# LEDDrive1.net
KiCad netlist of a schematic drawn in Altium Designer
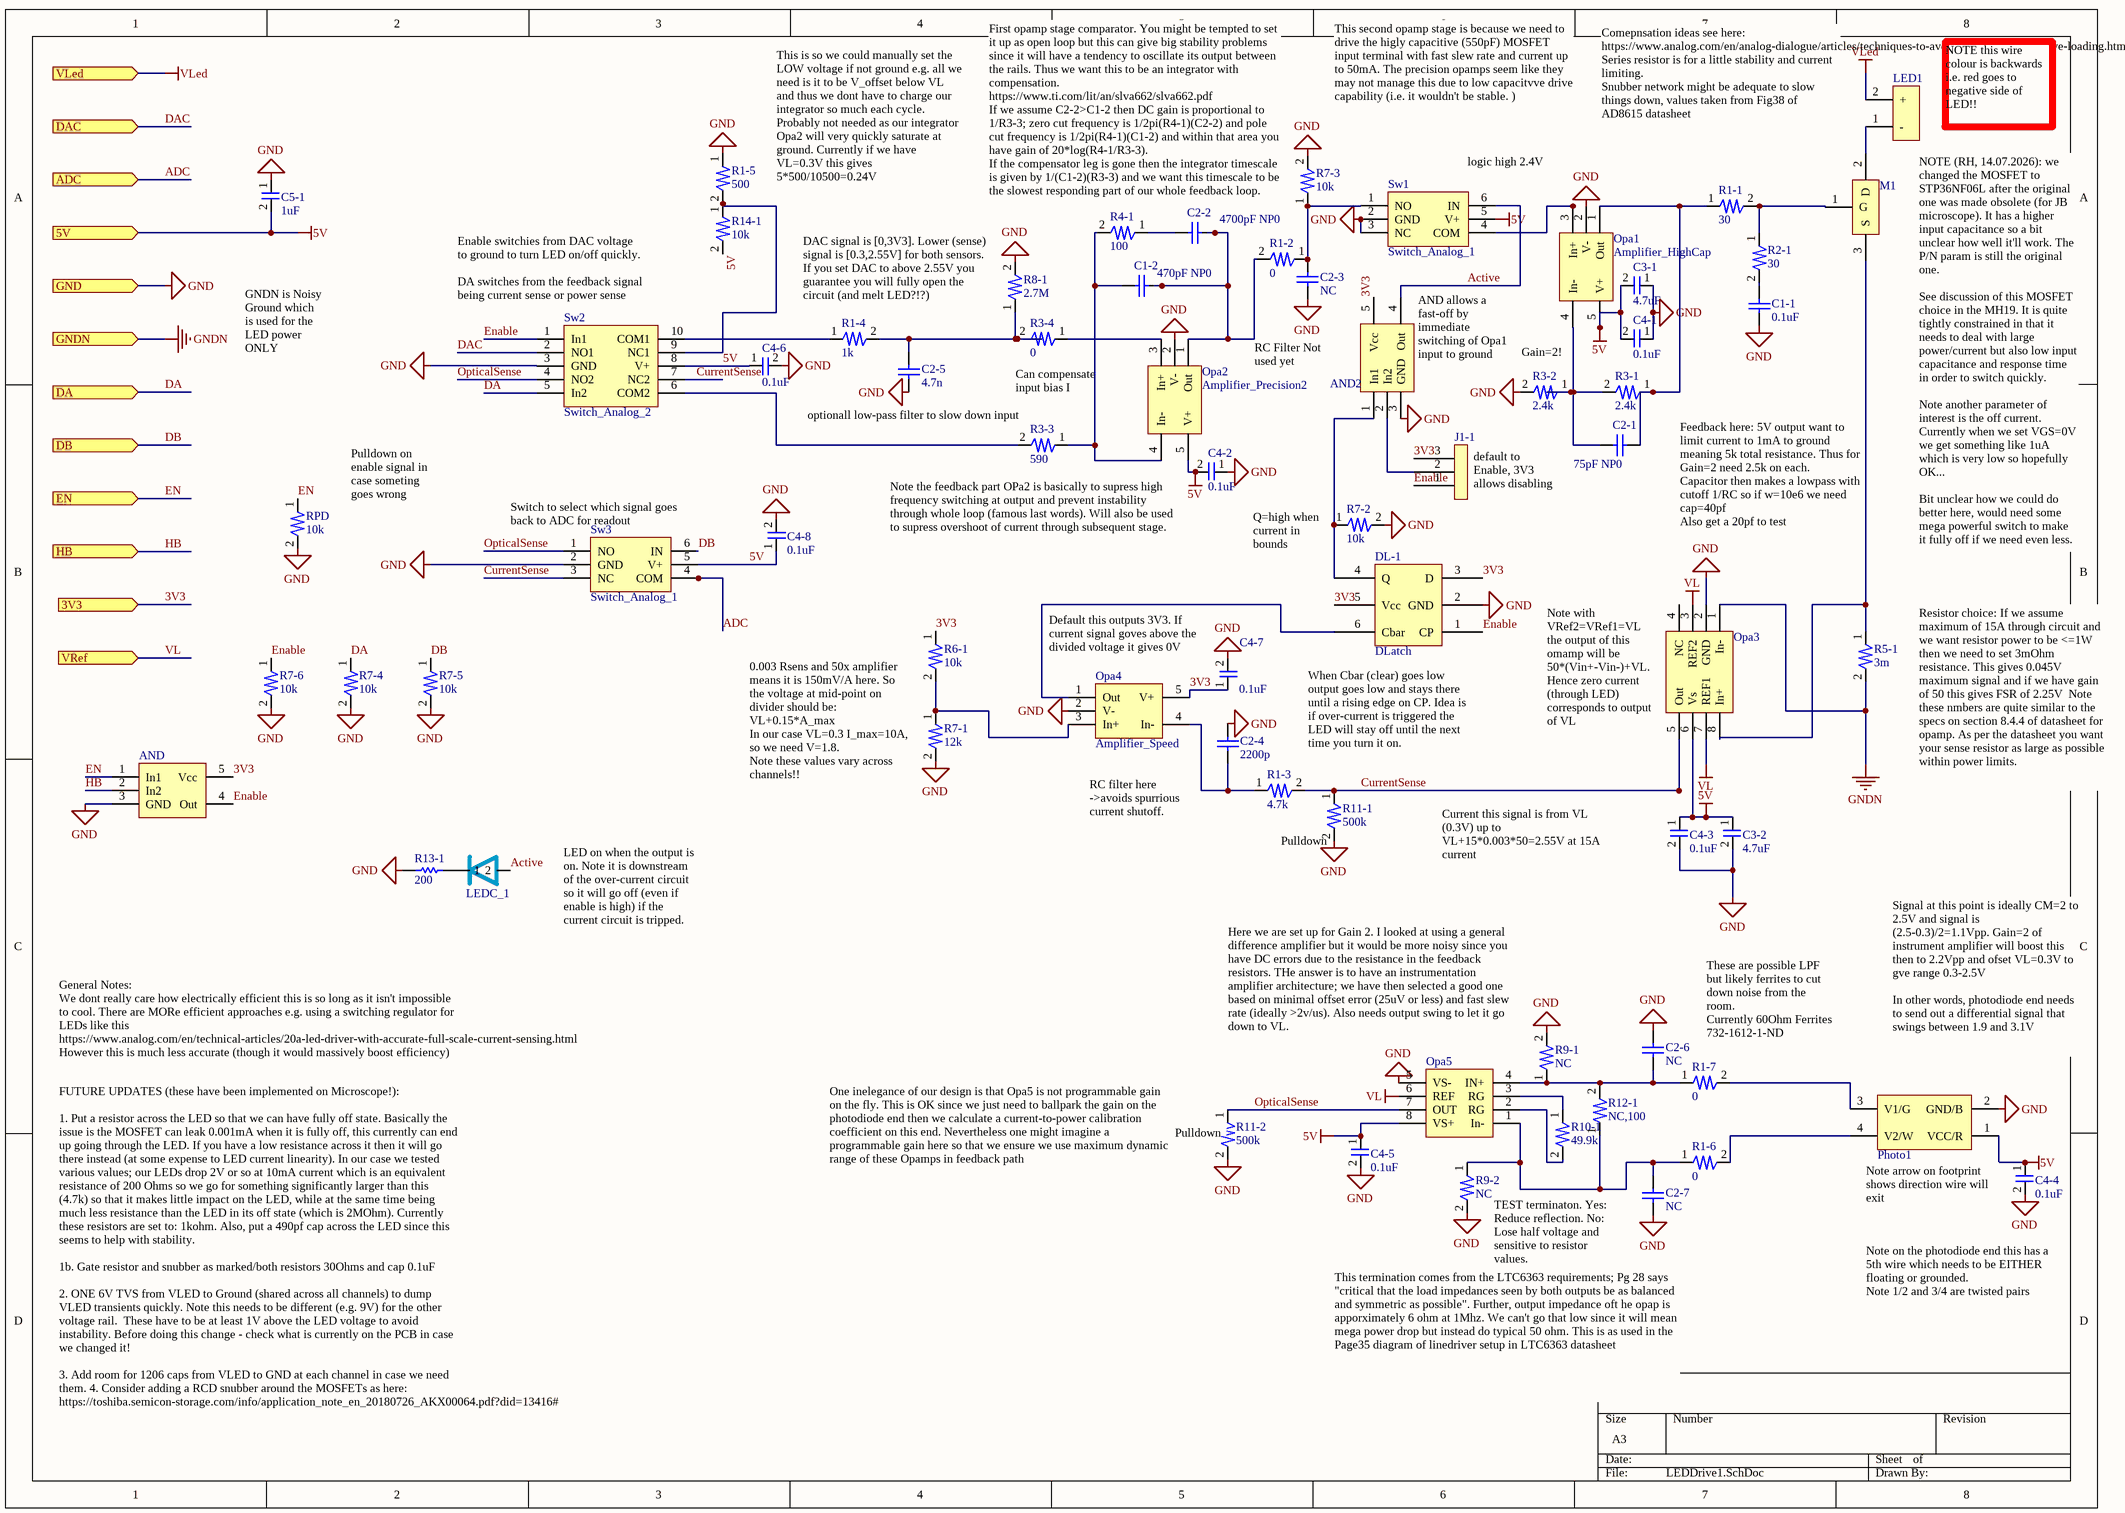
[diagram p0: LEDDrive1.SchDoc]

(export (version "E")
  (design (tool "Eeschema 10.0.6"))
  (components
    (comp (ref "AND")
      (value "AND_Gate")
      (footprint "SOT23-5")
      (libsource (lib "PCBSchematics") (part "AND_Gate"))
    )
    (comp (ref "AND2") (value "AND_Gate") (footprint "SOT23-5") (libsource (lib "") (part "AND_Gate_1")))
    (comp (ref "C1-1")
      (value "0.1uF")
      (footprint "0805")
      (description "Capacitor")
      (libsource (lib "Schlib1") (part "Cap 0805"))
    )
    (comp (ref "C1-2")
      (value "470pF NP0")
      (footprint "0805")
      (description "Capacitor")
      (libsource (lib "Schlib1") (part "Cap 0805"))
    )
    (comp (ref "C2-1")
      (value "75pF NP0")
      (footprint "0805")
      (description "Capacitor")
      (libsource (lib "Schlib1") (part "Cap 0805"))
    )
    (comp (ref "C2-2")
      (value "4700pF NP0")
      (footprint "0805")
      (description "Capacitor")
      (libsource (lib "Schlib1") (part "Cap 0805"))
    )
    (comp (ref "C2-3")
      (value "NC")
      (footprint "0805")
      (description "Capacitor")
      (libsource (lib "Schlib1") (part "Cap 0805"))
    )
    (comp (ref "C2-4")
      (value "2200p")
      (footprint "0805")
      (description "Capacitor")
      (libsource (lib "Schlib1") (part "Cap 0805"))
    )
    (comp (ref "C2-5")
      (value "4.7n")
      (footprint "0805")
      (description "Capacitor")
      (libsource (lib "Schlib1") (part "Cap 0805"))
    )
    (comp (ref "C2-6")
      (value "NC")
      (footprint "0805")
      (description "Capacitor")
      (libsource (lib "Schlib1") (part "Cap 0805"))
    )
    (comp (ref "C2-7")
      (value "NC")
      (footprint "0805")
      (description "Capacitor")
      (libsource (lib "Schlib1") (part "Cap 0805"))
    )
    (comp (ref "C3-1")
      (value "4.7uF")
      (footprint "0805")
      (libsource (lib "PCBSchematics") (part "Capacitor1"))
    )
    (comp (ref "C3-2")
      (value "4.7uF")
      (footprint "0805")
      (libsource (lib "PCBSchematics") (part "Capacitor1"))
    )
    (comp (ref "C4-1")
      (value "0.1uF")
      (footprint "0805")
      (libsource (lib "PCBSchematics") (part "Capacitor1"))
    )
    (comp (ref "C4-2")
      (value "0.1uF")
      (footprint "0805")
      (libsource (lib "PCBSchematics") (part "Capacitor1"))
    )
    (comp (ref "C4-3")
      (value "0.1uF")
      (footprint "0805")
      (libsource (lib "PCBSchematics") (part "Capacitor1"))
    )
    (comp (ref "C4-4")
      (value "0.1uF")
      (footprint "0805")
      (libsource (lib "PCBSchematics") (part "Capacitor1"))
    )
    (comp (ref "C4-5")
      (value "0.1uF")
      (footprint "0805")
      (libsource (lib "PCBSchematics") (part "Capacitor1"))
    )
    (comp (ref "C4-6")
      (value "0.1uF")
      (footprint "0805")
      (libsource (lib "PCBSchematics") (part "Capacitor1"))
    )
    (comp (ref "C4-7")
      (value "0.1uF")
      (footprint "0805")
      (libsource (lib "PCBSchematics") (part "Capacitor1"))
    )
    (comp (ref "C4-8")
      (value "0.1uF")
      (footprint "0805")
      (libsource (lib "PCBSchematics") (part "Capacitor1"))
    )
    (comp (ref "C5-1") (value "1uF") (footprint "0805") (libsource (lib "PCBSchematics") (part "Capacitor1")))
    (comp (ref "DL-1")
      (value "DLatch")
      (footprint "6-TSSOP / SC-70-6")
      (description "D-Latch")
      (libsource (lib "Schlib1") (part "DLatch"))
    )
    (comp (ref "J1-1")
      (value "Jumper3B")
      (footprint "Jumper3B")
      (libsource (lib "PCBSchematics") (part "Jumper3B"))
    )
    (comp (ref "LED1")
      (value "Header_Molex_Megafit")
      (footprint "Header Mini-Fit Jr 172648")
      (libsource (lib "PCBSchematics") (part "Header_Molex_Megafit"))
    )
    (comp (ref "LEDC_1")
      (value "LEDindicator")
      (footprint "LEDIndicator")
      (libsource (lib "Schlib1") (part "LEDindicator"))
    )
    (comp (ref "M1")
      (value "MOSFET-N-POWER")
      (footprint "MOSFET_w_Heatsink")
      (libsource (lib "PCBSchematics") (part "MOSFET-N-POWER"))
    )
    (comp (ref "Opa1")
      (value "Amplifier_HighCap")
      (footprint "SOT23-5")
      (libsource (lib "PCBSchematics") (part "Amplifier_HighCap"))
    )
    (comp (ref "Opa2")
      (value "Amplifier_Precision2")
      (footprint "SOT23-5")
      (libsource (lib "PCBSchematics") (part "Amplifier_Precision2"))
    )
    (comp (ref "Opa3")
      (value "Amplifier_Current")
      (footprint "8-TSSOP")
      (libsource (lib "PCBSchematics") (part "Amplifier_Current"))
    )
    (comp (ref "Opa4")
      (value "Amplifier_Speed")
      (footprint "SOT23-5")
      (libsource (lib "PCBSchematics") (part "Amplifier_Speed"))
    )
    (comp (ref "Opa5")
      (value "Amplifier_Instrumentation")
      (footprint "8-SOIC-NoHeatPad")
      (libsource (lib "PCBSchematics") (part "Amplifier_Instrumentation"))
    )
    (comp (ref "Photo1")
      (value "Connector_M5")
      (footprint "Connector_M5")
      (libsource (lib "PCBSchematics") (part "Connector_M5"))
    )
    (comp (ref "R1-1") (value "30") (footprint "0805") (libsource (lib "PCBSchematics") (part "Res1")))
    (comp (ref "R1-2") (value "0") (footprint "0805") (libsource (lib "PCBSchematics") (part "Res1")))
    (comp (ref "R1-3") (value "4.7k") (footprint "0805") (libsource (lib "PCBSchematics") (part "Res1")))
    (comp (ref "R1-4") (value "1k") (footprint "0805") (libsource (lib "PCBSchematics") (part "Res1")))
    (comp (ref "R1-5") (value "500") (footprint "0805") (libsource (lib "PCBSchematics") (part "Res1")))
    (comp (ref "R1-6") (value "0") (footprint "0805") (libsource (lib "PCBSchematics") (part "Res1")))
    (comp (ref "R1-7") (value "0") (footprint "0805") (libsource (lib "PCBSchematics") (part "Res1")))
    (comp (ref "R2-1") (value "30") (footprint "0805") (libsource (lib "PCBSchematics") (part "Res1")))
    (comp (ref "R3-1") (value "2.4k") (footprint "0805") (libsource (lib "PCBSchematics") (part "Res1")))
    (comp (ref "R3-2") (value "2.4k") (footprint "0805") (libsource (lib "PCBSchematics") (part "Res1")))
    (comp (ref "R3-3") (value "590") (footprint "0805") (libsource (lib "PCBSchematics") (part "Res1")))
    (comp (ref "R3-4") (value "0") (footprint "0805") (libsource (lib "PCBSchematics") (part "Res1")))
    (comp (ref "R4-1") (value "100") (footprint "0805") (libsource (lib "PCBSchematics") (part "Res1")))
    (comp (ref "R5-1") (value "3m") (footprint "2512") (libsource (lib "PCBSchematics") (part "Res1")))
    (comp (ref "R6-1") (value "10k") (footprint "0805") (libsource (lib "PCBSchematics") (part "Res1")))
    (comp (ref "R7-1") (value "12k") (footprint "0805") (libsource (lib "PCBSchematics") (part "Res1")))
    (comp (ref "R7-2") (value "10k") (footprint "0805") (libsource (lib "PCBSchematics") (part "Res1")))
    (comp (ref "R7-3") (value "10k") (footprint "0805") (libsource (lib "PCBSchematics") (part "Res1")))
    (comp (ref "R7-4") (value "10k") (footprint "0805") (libsource (lib "PCBSchematics") (part "Res1")))
    (comp (ref "R7-5") (value "10k") (footprint "0805") (libsource (lib "PCBSchematics") (part "Res1")))
    (comp (ref "R7-6") (value "10k") (footprint "0805") (libsource (lib "PCBSchematics") (part "Res1")))
    (comp (ref "R8-1") (value "2.7M") (footprint "0805") (libsource (lib "PCBSchematics") (part "Res1")))
    (comp (ref "R9-1") (value "NC") (footprint "0805") (libsource (lib "PCBSchematics") (part "Res1")))
    (comp (ref "R9-2") (value "NC") (footprint "0805") (libsource (lib "PCBSchematics") (part "Res1")))
    (comp (ref "R10-1") (value "49.9k") (footprint "0805") (libsource (lib "PCBSchematics") (part "Res1")))
    (comp (ref "R11-1") (value "500k") (footprint "0805") (libsource (lib "PCBSchematics") (part "Res1")))
    (comp (ref "R11-2") (value "500k") (footprint "0805") (libsource (lib "PCBSchematics") (part "Res1")))
    (comp (ref "R12-1") (value "NC,100") (footprint "0805") (libsource (lib "PCBSchematics") (part "Res1")))
    (comp (ref "R13-1")
      (value "200")
      (footprint "0603")
      (description "Resistor")
      (libsource (lib "Schlib1") (part "Res1"))
    )
    (comp (ref "R14-1") (value "10k") (footprint "0805") (libsource (lib "PCBSchematics") (part "Res1")))
    (comp (ref "RPD") (value "10k") (footprint "0603") (libsource (lib "PCBSchematics") (part "Res1")))
    (comp (ref "Sw1")
      (value "Switch_Analog_1")
      (footprint "SOT23-6")
      (libsource (lib "PCBSchematics") (part "Switch_Analog_1"))
    )
    (comp (ref "Sw2")
      (value "Switch_Analog_2")
      (footprint "10-VSSOP")
      (libsource (lib "PCBSchematics") (part "Switch_Analog_2"))
    )
    (comp (ref "Sw3")
      (value "Switch_Analog_1")
      (footprint "SOT23-6")
      (libsource (lib "PCBSchematics") (part "Switch_Analog_1"))
    )
  )
  (nets
    (net (code "1") (name "/3V3") (class "Default")
      (node (ref "AND") (pin "5") (pinfunction "Vcc_5") (pintype "passive"))
      (node (ref "AND2") (pin "5") (pinfunction "Vcc_5") (pintype "passive"))
      (node (ref "C4-7") (pin "1") (pinfunction "1_1") (pintype "passive"))
      (node (ref "DL-1") (pin "3") (pinfunction "D_3") (pintype "passive"))
      (node (ref "DL-1") (pin "5") (pinfunction "Vcc_5") (pintype "passive"))
      (node (ref "J1-1") (pin "3") (pinfunction "3_3") (pintype "passive"))
      (node (ref "Opa4") (pin "5") (pinfunction "V+_5") (pintype "passive"))
      (node (ref "R6-1") (pin "1") (pinfunction "1_1") (pintype "passive"))
    )
    (net (code "2") (name "/ADC") (class "Default")
      (node (ref "Sw3") (pin "4") (pinfunction "COM_4") (pintype "passive"))
    )
    (net (code "3") (name "/Active") (class "Default")
      (node (ref "AND2") (pin "4") (pinfunction "Out_4") (pintype "passive"))
      (node (ref "LEDC_1") (pin "2") (pinfunction "2_2") (pintype "passive"))
      (node (ref "Sw1") (pin "6") (pinfunction "IN_6") (pintype "passive"))
    )
    (net (code "4") (name "/CurrentSense") (class "Default")
      (node (ref "Opa3") (pin "5") (pinfunction "Out_5") (pintype "passive"))
      (node (ref "R1-3") (pin "2") (pinfunction "2_2") (pintype "passive"))
      (node (ref "R11-1") (pin "1") (pinfunction "1_1") (pintype "passive"))
      (node (ref "Sw2") (pin "7") (pinfunction "NC2_7") (pintype "passive"))
      (node (ref "Sw3") (pin "3") (pinfunction "NC_3") (pintype "passive"))
    )
    (net (code "5") (name "/DA") (class "Default")
      (node (ref "R7-4") (pin "1") (pinfunction "1_1") (pintype "passive"))
      (node (ref "Sw2") (pin "5") (pinfunction "In2_5") (pintype "passive"))
    )
    (net (code "6") (name "/DAC") (class "Default")
      (node (ref "Sw2") (pin "2") (pinfunction "NO1_2") (pintype "passive"))
    )
    (net (code "7") (name "/DB") (class "Default")
      (node (ref "R7-5") (pin "1") (pinfunction "1_1") (pintype "passive"))
      (node (ref "Sw3") (pin "6") (pinfunction "IN_6") (pintype "passive"))
    )
    (net (code "8") (name "/EN") (class "Default")
      (node (ref "AND") (pin "1") (pinfunction "In1_1") (pintype "passive"))
      (node (ref "RPD") (pin "1") (pinfunction "1_1") (pintype "passive"))
    )
    (net (code "9") (name "/Enable") (class "Default")
      (node (ref "AND") (pin "4") (pinfunction "Out_4") (pintype "passive"))
      (node (ref "DL-1") (pin "1") (pinfunction "CP_1") (pintype "passive"))
      (node (ref "J1-1") (pin "1") (pinfunction "1_1") (pintype "passive"))
      (node (ref "R7-6") (pin "1") (pinfunction "1_1") (pintype "passive"))
      (node (ref "Sw2") (pin "1") (pinfunction "In1_1") (pintype "passive"))
    )
    (net (code "10") (name "/HB") (class "Default")
      (node (ref "AND") (pin "2") (pinfunction "In2_2") (pintype "passive"))
    )
    (net (code "11") (name "/OpticalSense") (class "Default")
      (node (ref "Opa5") (pin "7") (pinfunction "OUT_7") (pintype "passive"))
      (node (ref "R11-2") (pin "1") (pinfunction "1_1") (pintype "passive"))
      (node (ref "Sw2") (pin "4") (pinfunction "NO2_4") (pintype "passive"))
      (node (ref "Sw3") (pin "1") (pinfunction "NO_1") (pintype "passive"))
    )
    (net (code "12") (name "5V") (class "Default")
      (node (ref "C3-1") (pin "2") (pinfunction "2_2") (pintype "passive"))
      (node (ref "C3-2") (pin "1") (pinfunction "1_1") (pintype "passive"))
      (node (ref "C4-1") (pin "2") (pinfunction "2_2") (pintype "passive"))
      (node (ref "C4-2") (pin "2") (pinfunction "2_2") (pintype "passive"))
      (node (ref "C4-3") (pin "1") (pinfunction "1_1") (pintype "passive"))
      (node (ref "C4-4") (pin "1") (pinfunction "1_1") (pintype "passive"))
      (node (ref "C4-5") (pin "1") (pinfunction "1_1") (pintype "passive"))
      (node (ref "C4-6") (pin "1") (pinfunction "1_1") (pintype "passive"))
      (node (ref "C4-8") (pin "1") (pinfunction "1_1") (pintype "passive"))
      (node (ref "C5-1") (pin "2") (pinfunction "2_2") (pintype "passive"))
      (node (ref "Opa1") (pin "5") (pinfunction "V+_5") (pintype "passive"))
      (node (ref "Opa2") (pin "5") (pinfunction "V+_5") (pintype "passive"))
      (node (ref "Opa3") (pin "6") (pinfunction "Vs_6") (pintype "passive"))
      (node (ref "Opa5") (pin "8") (pinfunction "VS+_8") (pintype "passive"))
      (node (ref "Photo1") (pin "1") (pinfunction "VCC/R_1") (pintype "passive"))
      (node (ref "R14-1") (pin "2") (pinfunction "2_2") (pintype "passive"))
      (node (ref "Sw1") (pin "5") (pinfunction "V+_5") (pintype "passive"))
      (node (ref "Sw2") (pin "8") (pinfunction "V+_8") (pintype "passive"))
      (node (ref "Sw3") (pin "5") (pinfunction "V+_5") (pintype "passive"))
    )
    (net (code "13") (name "GND") (class "Default")
      (node (ref "AND") (pin "3") (pinfunction "GND_3") (pintype "passive"))
      (node (ref "AND2") (pin "3") (pinfunction "GND_3") (pintype "passive"))
      (node (ref "C1-1") (pin "1") (pinfunction "1_1") (pintype "passive"))
      (node (ref "C2-3") (pin "1") (pinfunction "1_1") (pintype "passive"))
      (node (ref "C2-4") (pin "1") (pinfunction "1_1") (pintype "passive"))
      (node (ref "C2-5") (pin "2") (pinfunction "2_2") (pintype "passive"))
      (node (ref "C2-6") (pin "2") (pinfunction "2_2") (pintype "passive"))
      (node (ref "C2-7") (pin "2") (pinfunction "2_2") (pintype "passive"))
      (node (ref "C3-1") (pin "1") (pinfunction "1_1") (pintype "passive"))
      (node (ref "C3-2") (pin "2") (pinfunction "2_2") (pintype "passive"))
      (node (ref "C4-1") (pin "1") (pinfunction "1_1") (pintype "passive"))
      (node (ref "C4-2") (pin "1") (pinfunction "1_1") (pintype "passive"))
      (node (ref "C4-3") (pin "2") (pinfunction "2_2") (pintype "passive"))
      (node (ref "C4-4") (pin "2") (pinfunction "2_2") (pintype "passive"))
      (node (ref "C4-5") (pin "2") (pinfunction "2_2") (pintype "passive"))
      (node (ref "C4-6") (pin "2") (pinfunction "2_2") (pintype "passive"))
      (node (ref "C4-7") (pin "2") (pinfunction "2_2") (pintype "passive"))
      (node (ref "C4-8") (pin "2") (pinfunction "2_2") (pintype "passive"))
      (node (ref "C5-1") (pin "1") (pinfunction "1_1") (pintype "passive"))
      (node (ref "DL-1") (pin "2") (pinfunction "GND_2") (pintype "passive"))
      (node (ref "Opa1") (pin "2") (pinfunction "V-_2") (pintype "passive"))
      (node (ref "Opa2") (pin "2") (pinfunction "V-_2") (pintype "passive"))
      (node (ref "Opa3") (pin "2") (pinfunction "GND_2") (pintype "passive"))
      (node (ref "Opa4") (pin "2") (pinfunction "V-_2") (pintype "passive"))
      (node (ref "Opa5") (pin "5") (pinfunction "VS-_5") (pintype "passive"))
      (node (ref "Photo1") (pin "2") (pinfunction "GND/B_2") (pintype "passive"))
      (node (ref "R1-5") (pin "1") (pinfunction "1_1") (pintype "passive"))
      (node (ref "R11-1") (pin "2") (pinfunction "2_2") (pintype "passive"))
      (node (ref "R11-2") (pin "2") (pinfunction "2_2") (pintype "passive"))
      (node (ref "R13-1") (pin "2") (pinfunction "2_2") (pintype "passive"))
      (node (ref "R3-2") (pin "2") (pinfunction "2_2") (pintype "passive"))
      (node (ref "R7-1") (pin "2") (pinfunction "2_2") (pintype "passive"))
      (node (ref "R7-2") (pin "2") (pinfunction "2_2") (pintype "passive"))
      (node (ref "R7-3") (pin "2") (pinfunction "2_2") (pintype "passive"))
      (node (ref "R7-4") (pin "2") (pinfunction "2_2") (pintype "passive"))
      (node (ref "R7-5") (pin "2") (pinfunction "2_2") (pintype "passive"))
      (node (ref "R7-6") (pin "2") (pinfunction "2_2") (pintype "passive"))
      (node (ref "R8-1") (pin "2") (pinfunction "2_2") (pintype "passive"))
      (node (ref "R9-1") (pin "2") (pinfunction "2_2") (pintype "passive"))
      (node (ref "R9-2") (pin "2") (pinfunction "2_2") (pintype "passive"))
      (node (ref "RPD") (pin "2") (pinfunction "2_2") (pintype "passive"))
      (node (ref "Sw1") (pin "2") (pinfunction "GND_2") (pintype "passive"))
      (node (ref "Sw1") (pin "3") (pinfunction "NC_3") (pintype "passive"))
      (node (ref "Sw2") (pin "3") (pinfunction "GND_3") (pintype "passive"))
      (node (ref "Sw3") (pin "2") (pinfunction "GND_2") (pintype "passive"))
    )
    (net (code "14") (name "GNDN") (class "Default")
      (node (ref "Opa3") (pin "1") (pinfunction "In-_1") (pintype "passive"))
      (node (ref "R5-1") (pin "2") (pinfunction "2_2") (pintype "passive"))
    )
    (net (code "15") (name "Net-(AND2-In1)") (class "Default")
      (node (ref "AND2") (pin "1") (pinfunction "In1_1") (pintype "passive"))
      (node (ref "DL-1") (pin "4") (pinfunction "Q_4") (pintype "passive"))
      (node (ref "R7-2") (pin "1") (pinfunction "1_1") (pintype "passive"))
    )
    (net (code "16") (name "Net-(AND2-In2)") (class "Default")
      (node (ref "AND2") (pin "2") (pinfunction "In2_2") (pintype "passive"))
      (node (ref "J1-1") (pin "2") (pinfunction "2_2") (pintype "passive"))
    )
    (net (code "17") (name "Net-(C1-1-Pad2)") (class "Default")
      (node (ref "C1-1") (pin "2") (pinfunction "2_2") (pintype "passive"))
      (node (ref "R2-1") (pin "2") (pinfunction "2_2") (pintype "passive"))
    )
    (net (code "18") (name "Net-(C2-2-Pad2)") (class "Default")
      (node (ref "C2-2") (pin "2") (pinfunction "2_2") (pintype "passive"))
      (node (ref "R4-1") (pin "1") (pinfunction "1_1") (pintype "passive"))
    )
    (net (code "19") (name "Net-(C2-5-Pad1)") (class "Default")
      (node (ref "C2-5") (pin "1") (pinfunction "1_1") (pintype "passive"))
      (node (ref "R1-4") (pin "2") (pinfunction "2_2") (pintype "passive"))
      (node (ref "R3-4") (pin "2") (pinfunction "2_2") (pintype "passive"))
      (node (ref "R8-1") (pin "1") (pinfunction "1_1") (pintype "passive"))
    )
    (net (code "20") (name "Net-(DL-1-Cbar)") (class "Default")
      (node (ref "DL-1") (pin "6") (pinfunction "Cbar_6") (pintype "passive"))
      (node (ref "Opa4") (pin "1") (pinfunction "Out_1") (pintype "passive"))
    )
    (net (code "21") (name "Net-(LED1--)") (class "Default")
      (node (ref "LED1") (pin "1") (pinfunction "-_1") (pintype "passive"))
      (node (ref "M1") (pin "2") (pinfunction "D_2") (pintype "passive"))
    )
    (net (code "22") (name "Net-(LEDC_1-Pad1)") (class "Default")
      (node (ref "LEDC_1") (pin "1") (pinfunction "1_1") (pintype "passive"))
      (node (ref "R13-1") (pin "1") (pinfunction "1_1") (pintype "passive"))
    )
    (net (code "23") (name "Net-(M1-G)") (class "Default")
      (node (ref "M1") (pin "1") (pinfunction "G_1") (pintype "passive"))
      (node (ref "R1-1") (pin "2") (pinfunction "2_2") (pintype "passive"))
      (node (ref "R2-1") (pin "1") (pinfunction "1_1") (pintype "passive"))
    )
    (net (code "24") (name "Net-(M1-S)") (class "Default")
      (node (ref "M1") (pin "3") (pinfunction "S_3") (pintype "passive"))
      (node (ref "Opa3") (pin "8") (pinfunction "In+_8") (pintype "passive"))
      (node (ref "R5-1") (pin "1") (pinfunction "1_1") (pintype "passive"))
    )
    (net (code "25") (name "Net-(Opa1-In+)") (class "Default")
      (node (ref "Opa1") (pin "3") (pinfunction "In+_3") (pintype "passive"))
      (node (ref "Sw1") (pin "4") (pinfunction "COM_4") (pintype "passive"))
    )
    (net (code "26") (name "Net-(Opa1-In-)") (class "Default")
      (node (ref "C2-1") (pin "2") (pinfunction "2_2") (pintype "passive"))
      (node (ref "Opa1") (pin "4") (pinfunction "In-_4") (pintype "passive"))
      (node (ref "R3-1") (pin "2") (pinfunction "2_2") (pintype "passive"))
      (node (ref "R3-2") (pin "1") (pinfunction "1_1") (pintype "passive"))
    )
    (net (code "27") (name "Net-(Opa1-Out)") (class "Default")
      (node (ref "C2-1") (pin "1") (pinfunction "1_1") (pintype "passive"))
      (node (ref "Opa1") (pin "1") (pinfunction "Out_1") (pintype "passive"))
      (node (ref "R1-1") (pin "1") (pinfunction "1_1") (pintype "passive"))
      (node (ref "R3-1") (pin "1") (pinfunction "1_1") (pintype "passive"))
    )
    (net (code "28") (name "Net-(Opa2-In+)") (class "Default")
      (node (ref "Opa2") (pin "3") (pinfunction "In+_3") (pintype "passive"))
      (node (ref "R3-4") (pin "1") (pinfunction "1_1") (pintype "passive"))
    )
    (net (code "29") (name "Net-(Opa2-In-)") (class "Default")
      (node (ref "C1-2") (pin "2") (pinfunction "2_2") (pintype "passive"))
      (node (ref "Opa2") (pin "4") (pinfunction "In-_4") (pintype "passive"))
      (node (ref "R3-3") (pin "1") (pinfunction "1_1") (pintype "passive"))
      (node (ref "R4-1") (pin "2") (pinfunction "2_2") (pintype "passive"))
    )
    (net (code "30") (name "Net-(Opa2-Out)") (class "Default")
      (node (ref "C1-2") (pin "1") (pinfunction "1_1") (pintype "passive"))
      (node (ref "C2-2") (pin "1") (pinfunction "1_1") (pintype "passive"))
      (node (ref "Opa2") (pin "1") (pinfunction "Out_1") (pintype "passive"))
      (node (ref "R1-2") (pin "2") (pinfunction "2_2") (pintype "passive"))
    )
    (net (code "31") (name "Net-(Opa4-In+)") (class "Default")
      (node (ref "Opa4") (pin "3") (pinfunction "In+_3") (pintype "passive"))
      (node (ref "R6-1") (pin "2") (pinfunction "2_2") (pintype "passive"))
      (node (ref "R7-1") (pin "1") (pinfunction "1_1") (pintype "passive"))
    )
    (net (code "32") (name "Net-(Opa4-In-)") (class "Default")
      (node (ref "C2-4") (pin "2") (pinfunction "2_2") (pintype "passive"))
      (node (ref "Opa4") (pin "4") (pinfunction "In-_4") (pintype "passive"))
      (node (ref "R1-3") (pin "1") (pinfunction "1_1") (pintype "passive"))
    )
    (net (code "33") (name "Net-(Opa5-IN+)") (class "Default")
      (node (ref "C2-6") (pin "1") (pinfunction "1_1") (pintype "passive"))
      (node (ref "Opa5") (pin "4") (pinfunction "IN+_4") (pintype "passive"))
      (node (ref "R1-7") (pin "1") (pinfunction "1_1") (pintype "passive"))
      (node (ref "R12-1") (pin "2") (pinfunction "2_2") (pintype "passive"))
      (node (ref "R9-1") (pin "1") (pinfunction "1_1") (pintype "passive"))
    )
    (net (code "34") (name "Net-(Opa5-In-)") (class "Default")
      (node (ref "C2-7") (pin "1") (pinfunction "1_1") (pintype "passive"))
      (node (ref "Opa5") (pin "1") (pinfunction "In-_1") (pintype "passive"))
      (node (ref "R1-6") (pin "1") (pinfunction "1_1") (pintype "passive"))
      (node (ref "R12-1") (pin "1") (pinfunction "1_1") (pintype "passive"))
      (node (ref "R9-2") (pin "1") (pinfunction "1_1") (pintype "passive"))
    )
    (net (code "35") (name "Net-(Opa5-RG-Pad2)") (class "Default")
      (node (ref "Opa5") (pin "2") (pinfunction "RG_2") (pintype "passive"))
      (node (ref "R10-1") (pin "2") (pinfunction "2_2") (pintype "passive"))
    )
    (net (code "36") (name "Net-(Opa5-RG-Pad3)") (class "Default")
      (node (ref "Opa5") (pin "3") (pinfunction "RG_3") (pintype "passive"))
      (node (ref "R10-1") (pin "1") (pinfunction "1_1") (pintype "passive"))
    )
    (net (code "37") (name "Net-(Photo1-V1{slash}G)") (class "Default")
      (node (ref "Photo1") (pin "3") (pinfunction "V1/G_3") (pintype "passive"))
      (node (ref "R1-7") (pin "2") (pinfunction "2_2") (pintype "passive"))
    )
    (net (code "38") (name "Net-(Photo1-V2{slash}W)") (class "Default")
      (node (ref "Photo1") (pin "4") (pinfunction "V2/W_4") (pintype "passive"))
      (node (ref "R1-6") (pin "2") (pinfunction "2_2") (pintype "passive"))
    )
    (net (code "39") (name "Net-(Sw1-NO)") (class "Default")
      (node (ref "C2-3") (pin "2") (pinfunction "2_2") (pintype "passive"))
      (node (ref "R1-2") (pin "1") (pinfunction "1_1") (pintype "passive"))
      (node (ref "R7-3") (pin "1") (pinfunction "1_1") (pintype "passive"))
      (node (ref "Sw1") (pin "1") (pinfunction "NO_1") (pintype "passive"))
    )
    (net (code "40") (name "Net-(Sw2-COM1)") (class "Default")
      (node (ref "R1-4") (pin "1") (pinfunction "1_1") (pintype "passive"))
      (node (ref "Sw2") (pin "10") (pinfunction "COM1_10") (pintype "passive"))
    )
    (net (code "41") (name "Net-(Sw2-COM2)") (class "Default")
      (node (ref "R3-3") (pin "2") (pinfunction "2_2") (pintype "passive"))
      (node (ref "Sw2") (pin "6") (pinfunction "COM2_6") (pintype "passive"))
    )
    (net (code "42") (name "Net-(Sw2-NC1)") (class "Default")
      (node (ref "R1-5") (pin "2") (pinfunction "2_2") (pintype "passive"))
      (node (ref "R14-1") (pin "1") (pinfunction "1_1") (pintype "passive"))
      (node (ref "Sw2") (pin "9") (pinfunction "NC1_9") (pintype "passive"))
    )
    (net (code "43") (name "VL") (class "Default")
      (node (ref "Opa3") (pin "3") (pinfunction "REF2_3") (pintype "passive"))
      (node (ref "Opa3") (pin "7") (pinfunction "REF1_7") (pintype "passive"))
      (node (ref "Opa5") (pin "6") (pinfunction "REF_6") (pintype "passive"))
    )
    (net (code "44") (name "VLed") (class "Default")
      (node (ref "LED1") (pin "2") (pinfunction "+_2") (pintype "passive"))
    )
    (net (code "45") (name "unconnected-(Opa3-NC-Pad4)") (class "Default")
      (node (ref "Opa3") (pin "4") (pinfunction "NC_4") (pintype "passive"))
    )
  )
)
